# Micros.net
KiCad netlist of a schematic drawn in Altium Designer
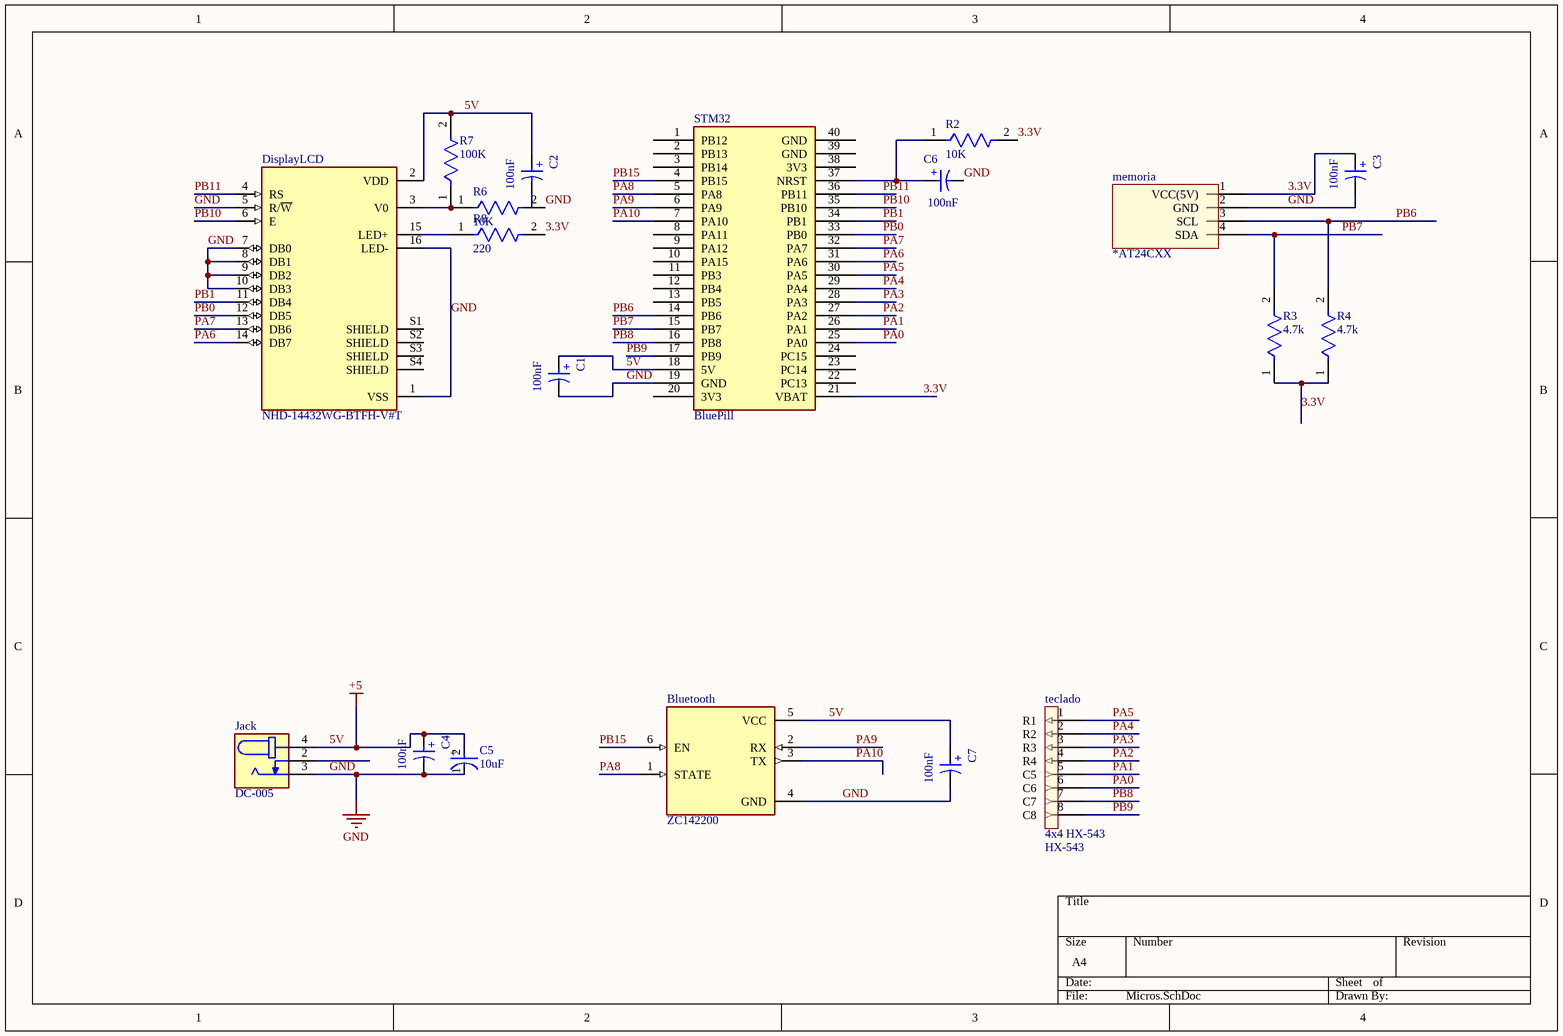
[diagram p0: Micros.SchDoc]

(export (version "E")
  (design (tool "Eeschema 10.0.6"))
  (components
    (comp (ref "Bluetooth")
      (value "ZC142200")
      (footprint "MODULE_ZC142200")
      (description "1pc HC-05 6 Pin Wireless Bluetooth RF Transceiver Module Serial For Arduino")
      (fields (field (name "MF") "YKS"))
      (libsource (lib "Mateus Maia") (part "ZC142200"))
    )
    (comp (ref "C1")
      (value "100nF")
      (footprint "WCAP-ATG8_D5H11")
      (description "Alum. Electrolytic Cap 100NF 63V 5MM Radial WCAP-ATG8; Lifetime 2000H +85°C")
      (fields (field (name "TOLERANCE") "20%"))
      (libsource (lib "Altium Content Vault") (part "Capacitor_Polarized"))
    )
    (comp (ref "C2")
      (value "100nF")
      (footprint "WCAP-ATG8_D5H11")
      (description "Alum. Electrolytic Cap 100NF 63V 5MM Radial WCAP-ATG8; Lifetime 2000H +85°C")
      (fields (field (name "TOLERANCE") "20%"))
      (libsource (lib "Altium Content Vault") (part "Capacitor_Polarized"))
    )
    (comp (ref "C3")
      (value "100nF")
      (footprint "WCAP-ATG8_D5H11")
      (description "Alum. Electrolytic Cap 100NF 63V 5MM Radial WCAP-ATG8; Lifetime 2000H +85°C")
      (fields (field (name "TOLERANCE") "20%"))
      (libsource (lib "Altium Content Vault") (part "Capacitor_Polarized"))
    )
    (comp (ref "C4")
      (value "100nF")
      (footprint "WCAP-ATG8_D5H11")
      (description "Alum. Electrolytic Cap 100NF 63V 5MM Radial WCAP-ATG8; Lifetime 2000H +85°C")
      (fields (field (name "TOLERANCE") "20%"))
      (libsource (lib "Altium Content Vault") (part "Capacitor_Polarized"))
    )
    (comp (ref "C5")
      (value "10uF")
      (footprint "FP-RAD-TH-D_5_0_5-L_11_1-MFG")
      (description "Aluminum Electrolytic Capacitors (Radial Lead Type) AEC-Q200 Qualified 10uF ±20% 50V")
      (fields (field (name "TOLERANCE") "20%"))
      (libsource (lib "Altium Content Vault") (part "a00bbbee19879c290e62620ae7e47b1"))
    )
    (comp (ref "C6")
      (value "100nF")
      (footprint "WCAP-ATG8_D5H11")
      (description "Alum. Electrolytic Cap 100NF 63V 5MM Radial WCAP-ATG8; Lifetime 2000H +85°C")
      (fields (field (name "TOLERANCE") "20%"))
      (libsource (lib "Altium Content Vault") (part "Capacitor_Polarized"))
    )
    (comp (ref "C7")
      (value "100nF")
      (footprint "WCAP-ATG8_D5H11")
      (description "Alum. Electrolytic Cap 100NF 63V 5MM Radial WCAP-ATG8; Lifetime 2000H +85°C")
      (fields (field (name "TOLERANCE") "20%"))
      (libsource (lib "Altium Content Vault") (part "Capacitor_Polarized"))
    )
    (comp (ref "DisplayLCD")
      (value "NHD-14432WG-BTFH-V#T")
      (footprint "LCD_NHD-14432WG-BTFH-V#T")
      (fields (field (name "MF") "Newhaven Display"))
      (libsource (lib "Mateus Maia") (part "NHD-14432WG-BTFH-V#T"))
    )
    (comp (ref "Jack")
      (value "DC-005")
      (footprint "NINIGI_DC-005")
      (description "DC Jack")
      (libsource (lib "Mateus Maia") (part "DC-005"))
    )
    (comp (ref "memoria")
      (value "memória")
      (footprint "memória")
      (description "AT24CXX")
      (fields (field (name "PARAMETER 1") "*AT24CXX"))
      (libsource (lib "micro") (part "memoria"))
    )
    (comp (ref "R2")
      (value "10K")
      (footprint "FP-MF0207-MFG")
      (description "RES 10K OHM 1% 0.6W AXIAL")
      (fields (field (name "TOLERANCE") "1%"))
      (libsource (lib "Altium Content Vault") (part "1029c3af85768c4190bb7ad29bc67b5"))
    )
    (comp (ref "R3")
      (value "4.7k")
      (footprint "FP-RCMM02-MFG")
      (description "RES 4.7K OHM 2% 1/2W AXIAL")
      (fields (field (name "TOLERANCE") "2%"))
      (libsource (lib "Altium Content Vault") (part "1029c3af85768c4190bb7ad29bc67b5"))
    )
    (comp (ref "R4")
      (value "4.7k")
      (footprint "FP-RCMM02-MFG")
      (description "RES 4.7K OHM 2% 1/2W AXIAL")
      (fields (field (name "TOLERANCE") "2%"))
      (libsource (lib "Altium Content Vault") (part "1029c3af85768c4190bb7ad29bc67b5"))
    )
    (comp (ref "R6")
      (value "10K")
      (footprint "FP-MF0207-MFG")
      (description "RES 10K OHM 1% 0.6W AXIAL")
      (fields (field (name "TOLERANCE") "1%"))
      (libsource (lib "Altium Content Vault") (part "1029c3af85768c4190bb7ad29bc67b5"))
    )
    (comp (ref "R7")
      (value "100K")
      (footprint "FP-PR02000201003JA100-MFG")
      (fields (field (name "TOLERANCE") "5%"))
      (libsource (lib "Altium Content Vault") (part "1029c3af85768c4190bb7ad29bc67b5"))
    )
    (comp (ref "R8")
      (value "220")
      (footprint "FP-MBA0204-MFG")
      (description "RES 220 OHM 0.4W 1% AXIAL")
      (fields
        (field (name "MANUFACTURER PART NUMBER") "MBA02040C2200FC100")
        (field (name "OCTOPART") "https://octopart.com/mba02040c2200fc100-vishay-43743094")
      )
      (libsource (lib "Altium Content Vault") (part "1029c3af85768c4190bb7ad29bc67b5"))
    )
    (comp (ref "STM32")
      (value "BluePill")
      (footprint "Stm32 BluePill")
      (description "Designed By @Alixahedi")
      (libsource (lib "Mateus Maia") (part "BluePill"))
    )
    (comp (ref "teclado")
      (value "4x4 HX-543")
      (footprint "Teclado")
      (description "teclado 4x4 HX-543")
      (fields (field (name "ALTIUM_VALUE") "HX-543"))
      (libsource (lib "micro") (part "teclado"))
    )
  )
  (nets
    (net (code "1") (name "+5") (class "Default")
      (node (ref "Bluetooth") (pin "5") (pinfunction "VCC_5") (pintype "power_in"))
      (node (ref "C1") (pin "1") (pinfunction "P_1") (pintype "passive"))
      (node (ref "C2") (pin "1") (pinfunction "P_1") (pintype "passive"))
      (node (ref "C4") (pin "1") (pinfunction "P_1") (pintype "passive"))
      (node (ref "C5") (pin "2") (pinfunction "A_2") (pintype "passive"))
      (node (ref "C7") (pin "1") (pinfunction "P_1") (pintype "passive"))
      (node (ref "DisplayLCD") (pin "2") (pinfunction "VDD_2") (pintype "power_in"))
      (node (ref "Jack") (pin "4") (pinfunction "2_4") (pintype "passive"))
      (node (ref "R7") (pin "2") (pinfunction "2_2") (pintype "passive"))
      (node (ref "STM32") (pin "18") (pinfunction "5V_18") (pintype "passive"))
    )
    (net (code "2") (name "/3.3V") (class "Default")
      (node (ref "C3") (pin "1") (pinfunction "P_1") (pintype "passive"))
      (node (ref "R2") (pin "2") (pinfunction "2_2") (pintype "passive"))
      (node (ref "R3") (pin "1") (pinfunction "1_1") (pintype "passive"))
      (node (ref "R4") (pin "1") (pinfunction "1_1") (pintype "passive"))
      (node (ref "R8") (pin "2") (pinfunction "2_2") (pintype "passive"))
      (node (ref "STM32") (pin "21") (pinfunction "VBAT_21") (pintype "passive"))
      (node (ref "memoria") (pin "1") (pinfunction "VCC(5V)_1") (pintype "passive"))
    )
    (net (code "3") (name "/PA0") (class "Default")
      (node (ref "STM32") (pin "25") (pinfunction "PA0_25") (pintype "passive"))
      (node (ref "teclado") (pin "6") (pinfunction "C6_6") (pintype "output"))
    )
    (net (code "4") (name "/PA1") (class "Default")
      (node (ref "STM32") (pin "26") (pinfunction "PA1_26") (pintype "passive"))
      (node (ref "teclado") (pin "5") (pinfunction "C5_5") (pintype "output"))
    )
    (net (code "5") (name "/PA2") (class "Default")
      (node (ref "STM32") (pin "27") (pinfunction "PA2_27") (pintype "passive"))
      (node (ref "teclado") (pin "4") (pinfunction "R4_4") (pintype "input"))
    )
    (net (code "6") (name "/PA3") (class "Default")
      (node (ref "STM32") (pin "28") (pinfunction "PA3_28") (pintype "passive"))
      (node (ref "teclado") (pin "3") (pinfunction "R3_3") (pintype "input"))
    )
    (net (code "7") (name "/PA4") (class "Default")
      (node (ref "STM32") (pin "29") (pinfunction "PA4_29") (pintype "passive"))
      (node (ref "teclado") (pin "2") (pinfunction "R2_2") (pintype "input"))
    )
    (net (code "8") (name "/PA5") (class "Default")
      (node (ref "STM32") (pin "30") (pinfunction "PA5_30") (pintype "passive"))
      (node (ref "teclado") (pin "1") (pinfunction "R1_1") (pintype "input"))
    )
    (net (code "9") (name "/PA6") (class "Default")
      (node (ref "DisplayLCD") (pin "14") (pinfunction "DB7_14") (pintype "bidirectional"))
      (node (ref "STM32") (pin "31") (pinfunction "PA6_31") (pintype "passive"))
    )
    (net (code "10") (name "/PA7") (class "Default")
      (node (ref "DisplayLCD") (pin "13") (pinfunction "DB6_13") (pintype "bidirectional"))
      (node (ref "STM32") (pin "32") (pinfunction "PA7_32") (pintype "passive"))
    )
    (net (code "11") (name "/PA8") (class "Default")
      (node (ref "Bluetooth") (pin "1") (pinfunction "STATE_1") (pintype "input"))
      (node (ref "STM32") (pin "5") (pinfunction "PA8_5") (pintype "passive"))
    )
    (net (code "12") (name "/PA9") (class "Default")
      (node (ref "Bluetooth") (pin "2") (pinfunction "RX_2") (pintype "input"))
      (node (ref "STM32") (pin "6") (pinfunction "PA9_6") (pintype "passive"))
    )
    (net (code "13") (name "/PA10") (class "Default")
      (node (ref "Bluetooth") (pin "3") (pinfunction "TX_3") (pintype "output"))
      (node (ref "STM32") (pin "7") (pinfunction "PA10_7") (pintype "passive"))
    )
    (net (code "14") (name "/PB0") (class "Default")
      (node (ref "DisplayLCD") (pin "12") (pinfunction "DB5_12") (pintype "bidirectional"))
      (node (ref "STM32") (pin "33") (pinfunction "PB0_33") (pintype "passive"))
    )
    (net (code "15") (name "/PB1") (class "Default")
      (node (ref "DisplayLCD") (pin "11") (pinfunction "DB4_11") (pintype "bidirectional"))
      (node (ref "STM32") (pin "34") (pinfunction "PB1_34") (pintype "passive"))
    )
    (net (code "16") (name "/PB6") (class "Default")
      (node (ref "R4") (pin "2") (pinfunction "2_2") (pintype "passive"))
      (node (ref "STM32") (pin "14") (pinfunction "PB6_14") (pintype "passive"))
      (node (ref "memoria") (pin "3") (pinfunction "SCL_3") (pintype "passive"))
    )
    (net (code "17") (name "/PB7") (class "Default")
      (node (ref "R3") (pin "2") (pinfunction "2_2") (pintype "passive"))
      (node (ref "STM32") (pin "15") (pinfunction "PB7_15") (pintype "passive"))
      (node (ref "memoria") (pin "4") (pinfunction "SDA_4") (pintype "passive"))
    )
    (net (code "18") (name "/PB8") (class "Default")
      (node (ref "STM32") (pin "16") (pinfunction "PB8_16") (pintype "passive"))
      (node (ref "teclado") (pin "7") (pinfunction "C7_7") (pintype "output"))
    )
    (net (code "19") (name "/PB9") (class "Default")
      (node (ref "STM32") (pin "17") (pinfunction "PB9_17") (pintype "passive"))
      (node (ref "teclado") (pin "8") (pinfunction "C8_8") (pintype "output"))
    )
    (net (code "20") (name "/PB10") (class "Default")
      (node (ref "DisplayLCD") (pin "6") (pinfunction "E_6") (pintype "input"))
      (node (ref "STM32") (pin "35") (pinfunction "PB10_35") (pintype "passive"))
    )
    (net (code "21") (name "/PB11") (class "Default")
      (node (ref "DisplayLCD") (pin "4") (pinfunction "RS_4") (pintype "input"))
      (node (ref "STM32") (pin "36") (pinfunction "PB11_36") (pintype "passive"))
    )
    (net (code "22") (name "/PB15") (class "Default")
      (node (ref "Bluetooth") (pin "6") (pinfunction "EN_6") (pintype "input"))
      (node (ref "STM32") (pin "4") (pinfunction "PB15_4") (pintype "passive"))
    )
    (net (code "23") (name "GND") (class "Default")
      (node (ref "Bluetooth") (pin "4") (pinfunction "GND_4") (pintype "power_in"))
      (node (ref "C1") (pin "2") (pinfunction "N_2") (pintype "passive"))
      (node (ref "C3") (pin "2") (pinfunction "N_2") (pintype "passive"))
      (node (ref "C4") (pin "2") (pinfunction "N_2") (pintype "passive"))
      (node (ref "C5") (pin "1") (pinfunction "C_1") (pintype "passive"))
      (node (ref "C6") (pin "2") (pinfunction "N_2") (pintype "passive"))
      (node (ref "C7") (pin "2") (pinfunction "N_2") (pintype "passive"))
      (node (ref "DisplayLCD") (pin "1") (pinfunction "VSS_1") (pintype "power_in"))
      (node (ref "DisplayLCD") (pin "10") (pinfunction "DB3_10") (pintype "bidirectional"))
      (node (ref "DisplayLCD") (pin "16") (pinfunction "LED-_16") (pintype "passive"))
      (node (ref "DisplayLCD") (pin "5") (pinfunction "R/~{W}_5") (pintype "input"))
      (node (ref "DisplayLCD") (pin "7") (pinfunction "DB0_7") (pintype "bidirectional"))
      (node (ref "DisplayLCD") (pin "8") (pinfunction "DB1_8") (pintype "bidirectional"))
      (node (ref "DisplayLCD") (pin "9") (pinfunction "DB2_9") (pintype "bidirectional"))
      (node (ref "Jack") (pin "3") (pinfunction "5_3") (pintype "passive"))
      (node (ref "R6") (pin "2") (pinfunction "2_2") (pintype "passive"))
      (node (ref "STM32") (pin "19") (pinfunction "GND_19") (pintype "passive"))
      (node (ref "memoria") (pin "2") (pinfunction "GND_2") (pintype "passive"))
    )
    (net (code "24") (name "Net-(C6-P)") (class "Default")
      (node (ref "C6") (pin "1") (pinfunction "P_1") (pintype "passive"))
      (node (ref "R2") (pin "1") (pinfunction "1_1") (pintype "passive"))
      (node (ref "STM32") (pin "37") (pinfunction "NRST_37") (pintype "passive"))
    )
    (net (code "25") (name "Net-(DisplayLCD-LED+)") (class "Default")
      (node (ref "DisplayLCD") (pin "15") (pinfunction "LED+_15") (pintype "passive"))
      (node (ref "R8") (pin "1") (pinfunction "1_1") (pintype "passive"))
    )
    (net (code "26") (name "Net-(DisplayLCD-V0)") (class "Default")
      (node (ref "DisplayLCD") (pin "3") (pinfunction "V0_3") (pintype "passive"))
      (node (ref "R6") (pin "1") (pinfunction "1_1") (pintype "passive"))
      (node (ref "R7") (pin "1") (pinfunction "1_1") (pintype "passive"))
    )
    (net (code "27") (name "unconnected-(C2-N-Pad2)") (class "Default")
      (node (ref "C2") (pin "2") (pinfunction "N_2") (pintype "passive"))
    )
    (net (code "28") (name "unconnected-(DisplayLCD-SHIELD-PadS1)") (class "Default")
      (node (ref "DisplayLCD") (pin "S1") (pinfunction "SHIELD_S1") (pintype "passive"))
    )
    (net (code "29") (name "unconnected-(DisplayLCD-SHIELD-PadS2)") (class "Default")
      (node (ref "DisplayLCD") (pin "S2") (pinfunction "SHIELD_S2") (pintype "passive"))
    )
    (net (code "30") (name "unconnected-(DisplayLCD-SHIELD-PadS3)") (class "Default")
      (node (ref "DisplayLCD") (pin "S3") (pinfunction "SHIELD_S3") (pintype "passive"))
    )
    (net (code "31") (name "unconnected-(DisplayLCD-SHIELD-PadS4)") (class "Default")
      (node (ref "DisplayLCD") (pin "S4") (pinfunction "SHIELD_S4") (pintype "passive"))
    )
    (net (code "32") (name "unconnected-(Jack-4-Pad2)") (class "Default")
      (node (ref "Jack") (pin "2") (pinfunction "4_2") (pintype "passive"))
    )
    (net (code "33") (name "unconnected-(STM32-3V3-Pad20)") (class "Default")
      (node (ref "STM32") (pin "20") (pinfunction "3V3_20") (pintype "passive"))
    )
    (net (code "34") (name "unconnected-(STM32-3V3-Pad38)") (class "Default")
      (node (ref "STM32") (pin "38") (pinfunction "3V3_38") (pintype "passive"))
    )
    (net (code "35") (name "unconnected-(STM32-GND-Pad39)") (class "Default")
      (node (ref "STM32") (pin "39") (pinfunction "GND_39") (pintype "passive"))
    )
    (net (code "36") (name "unconnected-(STM32-GND-Pad40)") (class "Default")
      (node (ref "STM32") (pin "40") (pinfunction "GND_40") (pintype "passive"))
    )
    (net (code "37") (name "unconnected-(STM32-PA11-Pad8)") (class "Default")
      (node (ref "STM32") (pin "8") (pinfunction "PA11_8") (pintype "passive"))
    )
    (net (code "38") (name "unconnected-(STM32-PA12-Pad9)") (class "Default")
      (node (ref "STM32") (pin "9") (pinfunction "PA12_9") (pintype "passive"))
    )
    (net (code "39") (name "unconnected-(STM32-PA15-Pad10)") (class "Default")
      (node (ref "STM32") (pin "10") (pinfunction "PA15_10") (pintype "passive"))
    )
    (net (code "40") (name "unconnected-(STM32-PB3-Pad11)") (class "Default")
      (node (ref "STM32") (pin "11") (pinfunction "PB3_11") (pintype "passive"))
    )
    (net (code "41") (name "unconnected-(STM32-PB4-Pad12)") (class "Default")
      (node (ref "STM32") (pin "12") (pinfunction "PB4_12") (pintype "passive"))
    )
    (net (code "42") (name "unconnected-(STM32-PB5-Pad13)") (class "Default")
      (node (ref "STM32") (pin "13") (pinfunction "PB5_13") (pintype "passive"))
    )
    (net (code "43") (name "unconnected-(STM32-PB12-Pad1)") (class "Default")
      (node (ref "STM32") (pin "1") (pinfunction "PB12_1") (pintype "passive"))
    )
    (net (code "44") (name "unconnected-(STM32-PB13-Pad2)") (class "Default")
      (node (ref "STM32") (pin "2") (pinfunction "PB13_2") (pintype "passive"))
    )
    (net (code "45") (name "unconnected-(STM32-PB14-Pad3)") (class "Default")
      (node (ref "STM32") (pin "3") (pinfunction "PB14_3") (pintype "passive"))
    )
    (net (code "46") (name "unconnected-(STM32-PC13-Pad22)") (class "Default")
      (node (ref "STM32") (pin "22") (pinfunction "PC13_22") (pintype "passive"))
    )
    (net (code "47") (name "unconnected-(STM32-PC14-Pad23)") (class "Default")
      (node (ref "STM32") (pin "23") (pinfunction "PC14_23") (pintype "passive"))
    )
    (net (code "48") (name "unconnected-(STM32-PC15-Pad24)") (class "Default")
      (node (ref "STM32") (pin "24") (pinfunction "PC15_24") (pintype "passive"))
    )
  )
)
